# ParticleBase.net
KiCad netlist of a schematic drawn in EAGLE
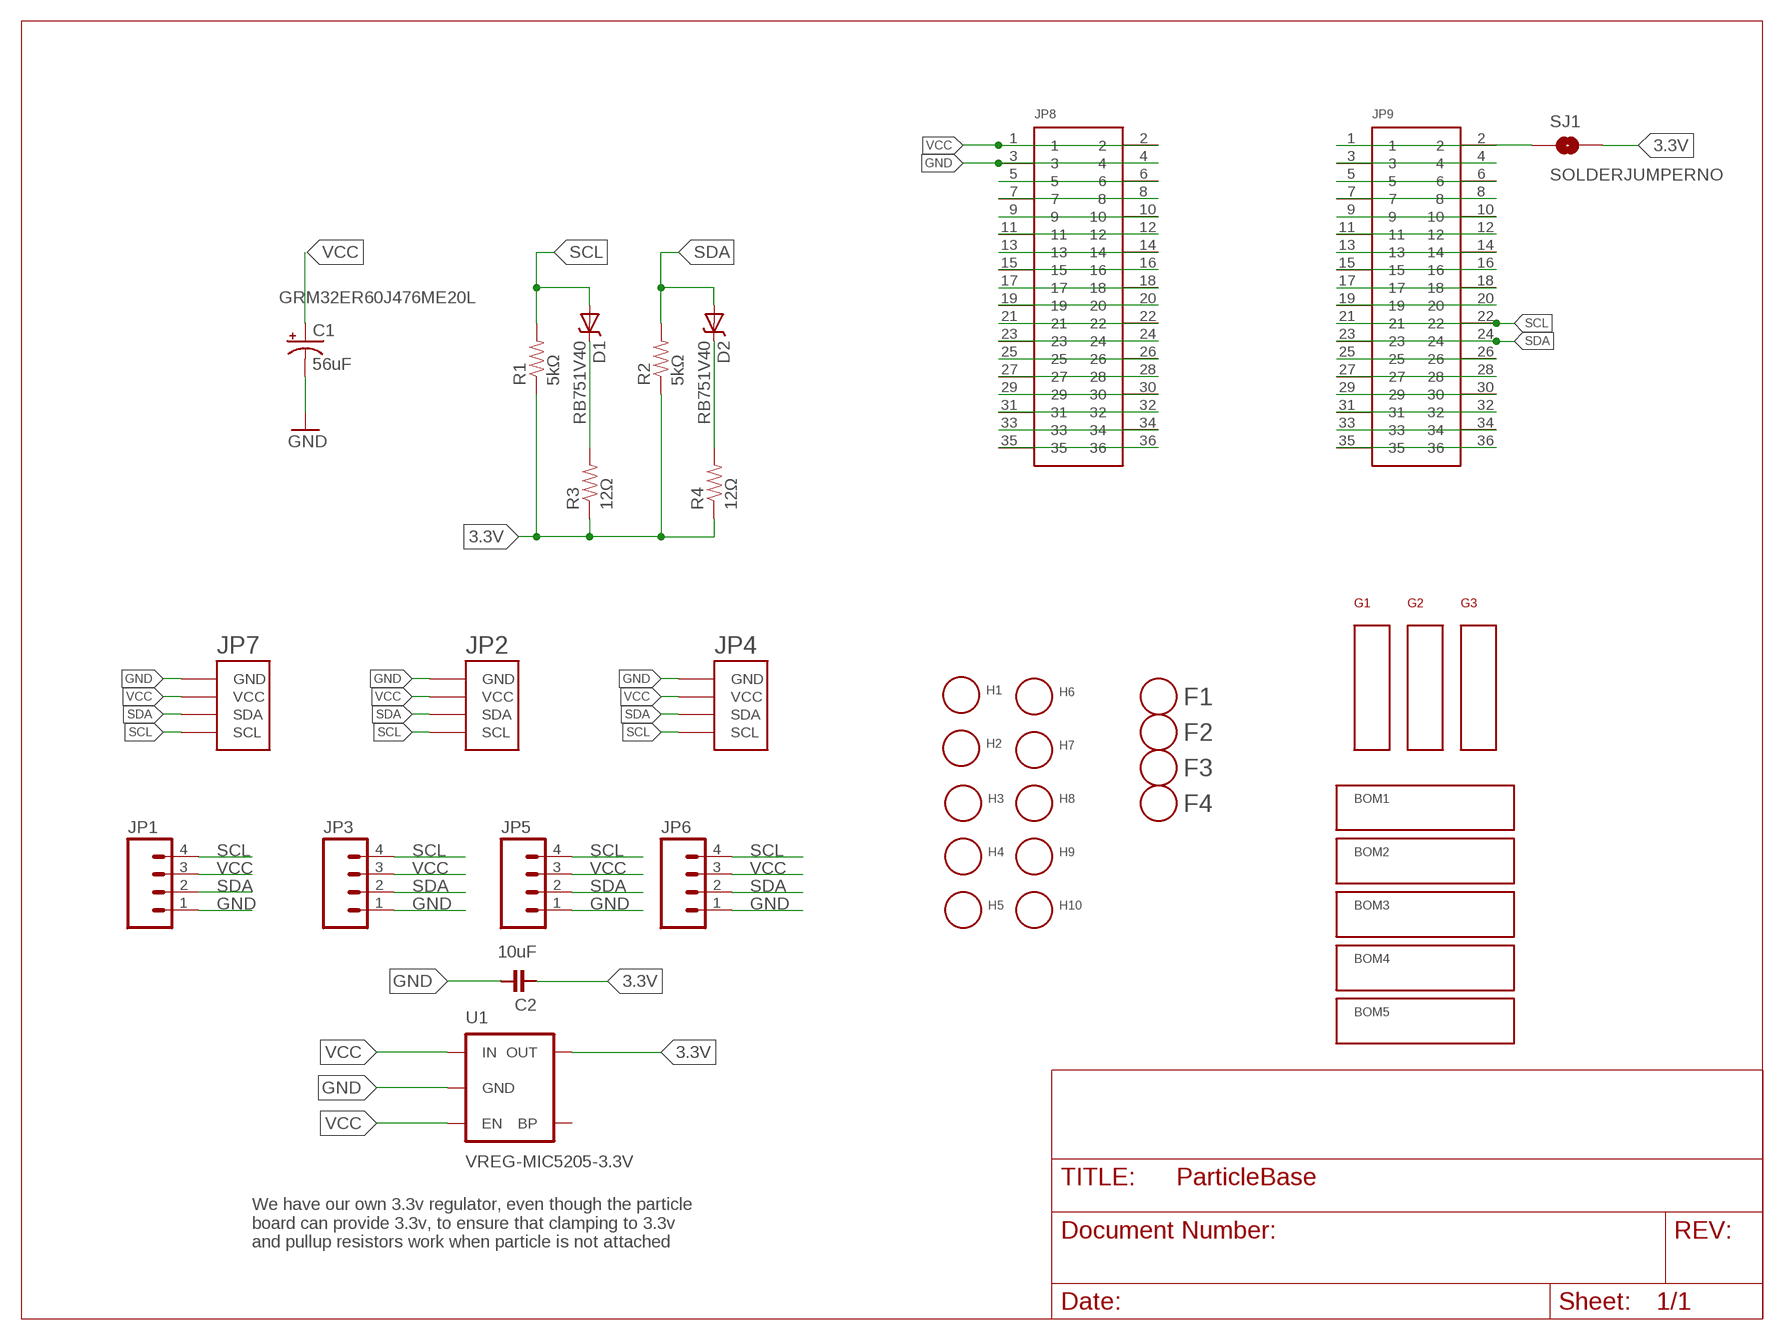
[diagram p0: schematic, sheet 1]

(export (version "E")
  (design (tool "Eeschema 10.0.6"))
  (components
    (comp (ref "C1")
      (value "56uF")
      (footprint "eagle-import:PANASONIC_D")
      (fields (field (name "PARTNUM") "EMVA250ADA560MF55G"))
      (libsource (lib "eagle-import") (part "CAPACITOR-POL-56UF-25V"))
    )
    (comp (ref "C2")
      (value "10uF")
      (footprint "eagle-import:0603")
      (fields (field (name "PARTNUM") "GRM188R61C106MA73D"))
      (libsource (lib "eagle-import") (part "CAPACITOR-10UF"))
    )
    (comp (ref "D1")
      (value "RB751V40")
      (footprint "eagle-import:SOD-323")
      (fields (field (name "PARTNUM") "BAT60A") (field (name "PARTNUM_1") "RB751V40"))
      (libsource (lib "eagle-import") (part "DIODE-SCHOTTKY-BAT60A"))
    )
    (comp (ref "D2")
      (value "RB751V40")
      (footprint "eagle-import:SOD-323")
      (fields (field (name "PARTNUM") "BAT60A") (field (name "PARTNUM_1") "RB751V40"))
      (libsource (lib "eagle-import") (part "DIODE-SCHOTTKY-BAT60A"))
    )
    (comp (ref "F1")
      (value "FIDUCIAL")
      (footprint "eagle-import:FIDUCIAL_1MM")
      (libsource (lib "eagle-import") (part "FIDUCIAL"))
    )
    (comp (ref "F2")
      (value "FIDUCIAL")
      (footprint "eagle-import:FIDUCIAL_1MM")
      (libsource (lib "eagle-import") (part "FIDUCIAL"))
    )
    (comp (ref "F3")
      (value "FIDUCIAL")
      (footprint "eagle-import:FIDUCIAL_1MM")
      (libsource (lib "eagle-import") (part "FIDUCIAL"))
    )
    (comp (ref "F4")
      (value "FIDUCIAL")
      (footprint "eagle-import:FIDUCIAL_1MM")
      (libsource (lib "eagle-import") (part "FIDUCIAL"))
    )
    (comp (ref "G1")
      (value "CARD-GUIDE")
      (footprint "eagle-import:CARD-GUIDE-2")
      (fields (field (name "PARTNUM") "HCG-201-165"))
      (libsource (lib "eagle-import") (part "CARD-GUIDE"))
    )
    (comp (ref "G2")
      (value "CARD-GUIDE")
      (footprint "eagle-import:CARD-GUIDE-2")
      (fields (field (name "PARTNUM") "HCG-202-165"))
      (libsource (lib "eagle-import") (part "CARD-GUIDE"))
    )
    (comp (ref "G3")
      (value "CARD-GUIDE")
      (footprint "eagle-import:CARD-GUIDE-2")
      (fields (field (name "PARTNUM") "HCG-201-165"))
      (libsource (lib "eagle-import") (part "CARD-GUIDE"))
    )
    (comp (ref "H1")
      (value "HOLE#2")
      (footprint "eagle-import:HOLE-#2")
      (fields (field (name "PARTNUM") "EXCLUDE"))
      (libsource (lib "eagle-import") (part "HOLE#2"))
    )
    (comp (ref "H2")
      (value "HOLE#2")
      (footprint "eagle-import:HOLE-#2")
      (fields (field (name "PARTNUM") "EXCLUDE"))
      (libsource (lib "eagle-import") (part "HOLE#2"))
    )
    (comp (ref "H3")
      (value "HOLE#2")
      (footprint "eagle-import:HOLE-#2")
      (fields (field (name "PARTNUM") "EXCLUDE"))
      (libsource (lib "eagle-import") (part "HOLE#2"))
    )
    (comp (ref "H4")
      (value "HOLE#2")
      (footprint "eagle-import:HOLE-#2")
      (fields (field (name "PARTNUM") "EXCLUDE"))
      (libsource (lib "eagle-import") (part "HOLE#2"))
    )
    (comp (ref "H5")
      (value "HOLE#2")
      (footprint "eagle-import:HOLE-#2")
      (fields (field (name "PARTNUM") "EXCLUDE"))
      (libsource (lib "eagle-import") (part "HOLE#2"))
    )
    (comp (ref "H6")
      (value "HOLE#2")
      (footprint "eagle-import:HOLE-#2")
      (fields (field (name "PARTNUM") "EXCLUDE"))
      (libsource (lib "eagle-import") (part "HOLE#2"))
    )
    (comp (ref "H7")
      (value "HOLE#2")
      (footprint "eagle-import:HOLE-#2")
      (fields (field (name "PARTNUM") "EXCLUDE"))
      (libsource (lib "eagle-import") (part "HOLE#2"))
    )
    (comp (ref "H8")
      (value "HOLE#2")
      (footprint "eagle-import:HOLE-#2")
      (fields (field (name "PARTNUM") "EXCLUDE"))
      (libsource (lib "eagle-import") (part "HOLE#2"))
    )
    (comp (ref "H9")
      (value "HOLE#2")
      (footprint "eagle-import:HOLE-#2")
      (fields (field (name "PARTNUM") "EXCLUDE"))
      (libsource (lib "eagle-import") (part "HOLE#2"))
    )
    (comp (ref "H10")
      (value "HOLE#2")
      (footprint "eagle-import:HOLE-#2")
      (fields (field (name "PARTNUM") "EXCLUDE"))
      (libsource (lib "eagle-import") (part "HOLE#2"))
    )
    (comp (ref "JP1")
      (value "M04LOCK")
      (footprint "eagle-import:1X04_LOCK")
      (fields (field (name "PARTNUM") "M20-9750446"))
      (libsource (lib "eagle-import") (part "M04LOCK"))
    )
    (comp (ref "JP2")
      (value "HEADER-MODULO")
      (footprint "eagle-import:JST-PA-SIDE-SMD")
      (fields (field (name "PARTNUM") "4P-SMD-2.0-90D"))
      (libsource (lib "eagle-import") (part "HEADER-MODULO"))
    )
    (comp (ref "JP3")
      (value "M04LOCK")
      (footprint "eagle-import:1X04_LOCK")
      (fields (field (name "PARTNUM") "M20-9750446"))
      (libsource (lib "eagle-import") (part "M04LOCK"))
    )
    (comp (ref "JP4")
      (value "HEADER-MODULO")
      (footprint "eagle-import:JST-PA-SIDE-SMD")
      (fields (field (name "PARTNUM") "4P-SMD-2.0-90D"))
      (libsource (lib "eagle-import") (part "HEADER-MODULO"))
    )
    (comp (ref "JP5")
      (value "M04LOCK")
      (footprint "eagle-import:1X04_LOCK")
      (fields (field (name "PARTNUM") "M20-9750446"))
      (libsource (lib "eagle-import") (part "M04LOCK"))
    )
    (comp (ref "JP6")
      (value "M04LOCK")
      (footprint "eagle-import:1X04_LOCK")
      (fields (field (name "PARTNUM") "M20-9750446"))
      (libsource (lib "eagle-import") (part "M04LOCK"))
    )
    (comp (ref "JP7")
      (value "HEADER-MODULO")
      (footprint "eagle-import:JST-PA-SIDE-SMD")
      (fields (field (name "PARTNUM") "4P-SMD-2.0-90D"))
      (libsource (lib "eagle-import") (part "HEADER-MODULO"))
    )
    (comp (ref "JP8")
      (value "HEADER-2X18")
      (footprint "eagle-import:2X18-LOCK")
      (fields (field (name "PARTNUM") "PPTC182LFBN-RC") (field (name "PARTNUM_1") "12x2 Receptacle"))
      (libsource (lib "eagle-import") (part "HEADER-2X18"))
    )
    (comp (ref "JP9")
      (value "HEADER-2X18")
      (footprint "eagle-import:2X18-LOCK")
      (fields (field (name "PARTNUM") "PPTC182LFBN-RC") (field (name "PARTNUM_1") "12x2 Receptacle"))
      (libsource (lib "eagle-import") (part "HEADER-2X18"))
    )
    (comp (ref "R1")
      (value "5kΩ")
      (footprint "eagle-import:0603")
      (fields (field (name "PARTNUM") "ERJ-3EKF5101V"))
      (libsource (lib "eagle-import") (part "RESISTOR-5KΩ"))
    )
    (comp (ref "R2")
      (value "5kΩ")
      (footprint "eagle-import:0603")
      (fields (field (name "PARTNUM") "ERJ-3EKF5101V"))
      (libsource (lib "eagle-import") (part "RESISTOR-5KΩ"))
    )
    (comp (ref "R3")
      (value "12Ω")
      (footprint "eagle-import:0603")
      (fields (field (name "PARTNUM") "ERJ-PA3J120V"))
      (libsource (lib "eagle-import") (part "RESISTOR-12Ω"))
    )
    (comp (ref "R4")
      (value "12Ω")
      (footprint "eagle-import:0603")
      (fields (field (name "PARTNUM") "ERJ-PA3J120V"))
      (libsource (lib "eagle-import") (part "RESISTOR-12Ω"))
    )
    (comp (ref "SJ1")
      (value "SOLDERJUMPERNO")
      (footprint "eagle-import:SJ_2S-NO")
      (libsource (lib "eagle-import") (part "SOLDERJUMPERNO"))
    )
    (comp (ref "U1")
      (value "VREG-MIC5205-3.3V")
      (footprint "eagle-import:SOT23-5")
      (fields (field (name "PARTNUM") "MIC5205-3.3YM5 TR"))
      (libsource (lib "eagle-import") (part "VREG-MIC5205-3.3V"))
    )
  )
  (nets
    (net (code "1") (name "3.3V") (class "Default")
      (node (ref "C2") (pin "2") (pinfunction "2_2") (pintype "passive"))
      (node (ref "R1") (pin "1") (pinfunction "1_1") (pintype "passive"))
      (node (ref "R2") (pin "1") (pinfunction "1_1") (pintype "passive"))
      (node (ref "R3") (pin "1") (pinfunction "1_1") (pintype "passive"))
      (node (ref "R4") (pin "1") (pinfunction "1_1") (pintype "passive"))
      (node (ref "SJ1") (pin "2") (pinfunction "2_2") (pintype "passive"))
      (node (ref "U1") (pin "5") (pinfunction "OUT_5") (pintype "passive"))
    )
    (net (code "2") (name "GND") (class "Default")
      (node (ref "C1") (pin "-") (pinfunction "-_-") (pintype "passive"))
      (node (ref "C2") (pin "1") (pinfunction "1_1") (pintype "passive"))
      (node (ref "JP1") (pin "1") (pinfunction "1_1") (pintype "passive"))
      (node (ref "JP2") (pin "1") (pinfunction "GND_1") (pintype "bidirectional"))
      (node (ref "JP3") (pin "1") (pinfunction "1_1") (pintype "passive"))
      (node (ref "JP4") (pin "1") (pinfunction "GND_1") (pintype "bidirectional"))
      (node (ref "JP5") (pin "1") (pinfunction "1_1") (pintype "passive"))
      (node (ref "JP6") (pin "1") (pinfunction "1_1") (pintype "passive"))
      (node (ref "JP7") (pin "1") (pinfunction "GND_1") (pintype "bidirectional"))
      (node (ref "JP8") (pin "3") (pinfunction "3_3") (pintype "bidirectional"))
      (node (ref "JP8") (pin "4") (pinfunction "4_4") (pintype "bidirectional"))
      (node (ref "U1") (pin "2") (pinfunction "GND_2") (pintype "input"))
    )
    (net (code "3") (name "Net-(D1-PadC)") (class "Default")
      (node (ref "D1") (pin "C") (pinfunction "C_C") (pintype "passive"))
      (node (ref "R3") (pin "2") (pinfunction "2_2") (pintype "passive"))
    )
    (net (code "4") (name "Net-(D2-PadC)") (class "Default")
      (node (ref "D2") (pin "C") (pinfunction "C_C") (pintype "passive"))
      (node (ref "R4") (pin "2") (pinfunction "2_2") (pintype "passive"))
    )
    (net (code "5") (name "Net-(JP8-Pad5)") (class "Default")
      (node (ref "JP8") (pin "5") (pinfunction "5_5") (pintype "bidirectional"))
      (node (ref "JP8") (pin "6") (pinfunction "6_6") (pintype "bidirectional"))
    )
    (net (code "6") (name "Net-(JP8-Pad7)") (class "Default")
      (node (ref "JP8") (pin "7") (pinfunction "7_7") (pintype "bidirectional"))
      (node (ref "JP8") (pin "8") (pinfunction "8_8") (pintype "bidirectional"))
    )
    (net (code "7") (name "Net-(JP8-Pad10)") (class "Default")
      (node (ref "JP8") (pin "10") (pinfunction "10_10") (pintype "bidirectional"))
      (node (ref "JP8") (pin "9") (pinfunction "9_9") (pintype "bidirectional"))
    )
    (net (code "8") (name "Net-(JP8-Pad11)") (class "Default")
      (node (ref "JP8") (pin "11") (pinfunction "11_11") (pintype "bidirectional"))
      (node (ref "JP8") (pin "12") (pinfunction "12_12") (pintype "bidirectional"))
    )
    (net (code "9") (name "Net-(JP8-Pad13)") (class "Default")
      (node (ref "JP8") (pin "13") (pinfunction "13_13") (pintype "bidirectional"))
      (node (ref "JP8") (pin "14") (pinfunction "14_14") (pintype "bidirectional"))
    )
    (net (code "10") (name "Net-(JP8-Pad15)") (class "Default")
      (node (ref "JP8") (pin "15") (pinfunction "15_15") (pintype "bidirectional"))
      (node (ref "JP8") (pin "16") (pinfunction "16_16") (pintype "bidirectional"))
    )
    (net (code "11") (name "Net-(JP8-Pad17)") (class "Default")
      (node (ref "JP8") (pin "17") (pinfunction "17_17") (pintype "bidirectional"))
      (node (ref "JP8") (pin "18") (pinfunction "18_18") (pintype "bidirectional"))
    )
    (net (code "12") (name "Net-(JP8-Pad19)") (class "Default")
      (node (ref "JP8") (pin "19") (pinfunction "19_19") (pintype "bidirectional"))
      (node (ref "JP8") (pin "20") (pinfunction "20_20") (pintype "bidirectional"))
    )
    (net (code "13") (name "Net-(JP8-Pad21)") (class "Default")
      (node (ref "JP8") (pin "21") (pinfunction "21_21") (pintype "bidirectional"))
      (node (ref "JP8") (pin "22") (pinfunction "22_22") (pintype "bidirectional"))
    )
    (net (code "14") (name "Net-(JP8-Pad23)") (class "Default")
      (node (ref "JP8") (pin "23") (pinfunction "23_23") (pintype "bidirectional"))
      (node (ref "JP8") (pin "24") (pinfunction "24_24") (pintype "bidirectional"))
    )
    (net (code "15") (name "Net-(JP8-Pad25)") (class "Default")
      (node (ref "JP8") (pin "25") (pinfunction "25_25") (pintype "bidirectional"))
      (node (ref "JP8") (pin "26") (pinfunction "26_26") (pintype "bidirectional"))
    )
    (net (code "16") (name "Net-(JP8-Pad27)") (class "Default")
      (node (ref "JP8") (pin "27") (pinfunction "27_27") (pintype "bidirectional"))
      (node (ref "JP8") (pin "28") (pinfunction "28_28") (pintype "bidirectional"))
    )
    (net (code "17") (name "Net-(JP8-Pad29)") (class "Default")
      (node (ref "JP8") (pin "29") (pinfunction "29_29") (pintype "bidirectional"))
      (node (ref "JP8") (pin "30") (pinfunction "30_30") (pintype "bidirectional"))
    )
    (net (code "18") (name "Net-(JP8-Pad31)") (class "Default")
      (node (ref "JP8") (pin "31") (pinfunction "31_31") (pintype "bidirectional"))
      (node (ref "JP8") (pin "32") (pinfunction "32_32") (pintype "bidirectional"))
    )
    (net (code "19") (name "Net-(JP8-Pad33)") (class "Default")
      (node (ref "JP8") (pin "33") (pinfunction "33_33") (pintype "bidirectional"))
      (node (ref "JP8") (pin "34") (pinfunction "34_34") (pintype "bidirectional"))
    )
    (net (code "20") (name "Net-(JP8-Pad35)") (class "Default")
      (node (ref "JP8") (pin "35") (pinfunction "35_35") (pintype "bidirectional"))
      (node (ref "JP8") (pin "36") (pinfunction "36_36") (pintype "bidirectional"))
    )
    (net (code "21") (name "Net-(JP9-Pad1)") (class "Default")
      (node (ref "JP9") (pin "1") (pinfunction "1_1") (pintype "bidirectional"))
      (node (ref "JP9") (pin "2") (pinfunction "2_2") (pintype "bidirectional"))
      (node (ref "SJ1") (pin "1") (pinfunction "1_1") (pintype "passive"))
    )
    (net (code "22") (name "Net-(JP9-Pad3)") (class "Default")
      (node (ref "JP9") (pin "3") (pinfunction "3_3") (pintype "bidirectional"))
      (node (ref "JP9") (pin "4") (pinfunction "4_4") (pintype "bidirectional"))
    )
    (net (code "23") (name "Net-(JP9-Pad5)") (class "Default")
      (node (ref "JP9") (pin "5") (pinfunction "5_5") (pintype "bidirectional"))
      (node (ref "JP9") (pin "6") (pinfunction "6_6") (pintype "bidirectional"))
    )
    (net (code "24") (name "Net-(JP9-Pad7)") (class "Default")
      (node (ref "JP9") (pin "7") (pinfunction "7_7") (pintype "bidirectional"))
      (node (ref "JP9") (pin "8") (pinfunction "8_8") (pintype "bidirectional"))
    )
    (net (code "25") (name "Net-(JP9-Pad10)") (class "Default")
      (node (ref "JP9") (pin "10") (pinfunction "10_10") (pintype "bidirectional"))
      (node (ref "JP9") (pin "9") (pinfunction "9_9") (pintype "bidirectional"))
    )
    (net (code "26") (name "Net-(JP9-Pad11)") (class "Default")
      (node (ref "JP9") (pin "11") (pinfunction "11_11") (pintype "bidirectional"))
      (node (ref "JP9") (pin "12") (pinfunction "12_12") (pintype "bidirectional"))
    )
    (net (code "27") (name "Net-(JP9-Pad13)") (class "Default")
      (node (ref "JP9") (pin "13") (pinfunction "13_13") (pintype "bidirectional"))
      (node (ref "JP9") (pin "14") (pinfunction "14_14") (pintype "bidirectional"))
    )
    (net (code "28") (name "Net-(JP9-Pad15)") (class "Default")
      (node (ref "JP9") (pin "15") (pinfunction "15_15") (pintype "bidirectional"))
      (node (ref "JP9") (pin "16") (pinfunction "16_16") (pintype "bidirectional"))
    )
    (net (code "29") (name "Net-(JP9-Pad17)") (class "Default")
      (node (ref "JP9") (pin "17") (pinfunction "17_17") (pintype "bidirectional"))
      (node (ref "JP9") (pin "18") (pinfunction "18_18") (pintype "bidirectional"))
    )
    (net (code "30") (name "Net-(JP9-Pad19)") (class "Default")
      (node (ref "JP9") (pin "19") (pinfunction "19_19") (pintype "bidirectional"))
      (node (ref "JP9") (pin "20") (pinfunction "20_20") (pintype "bidirectional"))
    )
    (net (code "31") (name "Net-(JP9-Pad25)") (class "Default")
      (node (ref "JP9") (pin "25") (pinfunction "25_25") (pintype "bidirectional"))
      (node (ref "JP9") (pin "26") (pinfunction "26_26") (pintype "bidirectional"))
    )
    (net (code "32") (name "Net-(JP9-Pad27)") (class "Default")
      (node (ref "JP9") (pin "27") (pinfunction "27_27") (pintype "bidirectional"))
      (node (ref "JP9") (pin "28") (pinfunction "28_28") (pintype "bidirectional"))
    )
    (net (code "33") (name "Net-(JP9-Pad29)") (class "Default")
      (node (ref "JP9") (pin "29") (pinfunction "29_29") (pintype "bidirectional"))
      (node (ref "JP9") (pin "30") (pinfunction "30_30") (pintype "bidirectional"))
    )
    (net (code "34") (name "Net-(JP9-Pad31)") (class "Default")
      (node (ref "JP9") (pin "31") (pinfunction "31_31") (pintype "bidirectional"))
      (node (ref "JP9") (pin "32") (pinfunction "32_32") (pintype "bidirectional"))
    )
    (net (code "35") (name "Net-(JP9-Pad33)") (class "Default")
      (node (ref "JP9") (pin "33") (pinfunction "33_33") (pintype "bidirectional"))
      (node (ref "JP9") (pin "34") (pinfunction "34_34") (pintype "bidirectional"))
    )
    (net (code "36") (name "Net-(JP9-Pad35)") (class "Default")
      (node (ref "JP9") (pin "35") (pinfunction "35_35") (pintype "bidirectional"))
      (node (ref "JP9") (pin "36") (pinfunction "36_36") (pintype "bidirectional"))
    )
    (net (code "37") (name "SCL") (class "Default")
      (node (ref "D1") (pin "A") (pinfunction "A_A") (pintype "passive"))
      (node (ref "JP1") (pin "4") (pinfunction "4_4") (pintype "passive"))
      (node (ref "JP2") (pin "4") (pinfunction "SCL_4") (pintype "bidirectional"))
      (node (ref "JP3") (pin "4") (pinfunction "4_4") (pintype "passive"))
      (node (ref "JP4") (pin "4") (pinfunction "SCL_4") (pintype "bidirectional"))
      (node (ref "JP5") (pin "4") (pinfunction "4_4") (pintype "passive"))
      (node (ref "JP6") (pin "4") (pinfunction "4_4") (pintype "passive"))
      (node (ref "JP7") (pin "4") (pinfunction "SCL_4") (pintype "bidirectional"))
      (node (ref "JP9") (pin "21") (pinfunction "21_21") (pintype "bidirectional"))
      (node (ref "JP9") (pin "22") (pinfunction "22_22") (pintype "bidirectional"))
      (node (ref "R1") (pin "2") (pinfunction "2_2") (pintype "passive"))
    )
    (net (code "38") (name "SDA") (class "Default")
      (node (ref "D2") (pin "A") (pinfunction "A_A") (pintype "passive"))
      (node (ref "JP1") (pin "2") (pinfunction "2_2") (pintype "passive"))
      (node (ref "JP2") (pin "3") (pinfunction "SDA_3") (pintype "bidirectional"))
      (node (ref "JP3") (pin "2") (pinfunction "2_2") (pintype "passive"))
      (node (ref "JP4") (pin "3") (pinfunction "SDA_3") (pintype "bidirectional"))
      (node (ref "JP5") (pin "2") (pinfunction "2_2") (pintype "passive"))
      (node (ref "JP6") (pin "2") (pinfunction "2_2") (pintype "passive"))
      (node (ref "JP7") (pin "3") (pinfunction "SDA_3") (pintype "bidirectional"))
      (node (ref "JP9") (pin "23") (pinfunction "23_23") (pintype "bidirectional"))
      (node (ref "JP9") (pin "24") (pinfunction "24_24") (pintype "bidirectional"))
      (node (ref "R2") (pin "2") (pinfunction "2_2") (pintype "passive"))
    )
    (net (code "39") (name "VCC") (class "Default")
      (node (ref "C1") (pin "+") (pinfunction "+_+") (pintype "passive"))
      (node (ref "JP1") (pin "3") (pinfunction "3_3") (pintype "passive"))
      (node (ref "JP2") (pin "2") (pinfunction "VCC_2") (pintype "bidirectional"))
      (node (ref "JP3") (pin "3") (pinfunction "3_3") (pintype "passive"))
      (node (ref "JP4") (pin "2") (pinfunction "VCC_2") (pintype "bidirectional"))
      (node (ref "JP5") (pin "3") (pinfunction "3_3") (pintype "passive"))
      (node (ref "JP6") (pin "3") (pinfunction "3_3") (pintype "passive"))
      (node (ref "JP7") (pin "2") (pinfunction "VCC_2") (pintype "bidirectional"))
      (node (ref "JP8") (pin "1") (pinfunction "1_1") (pintype "bidirectional"))
      (node (ref "JP8") (pin "2") (pinfunction "2_2") (pintype "bidirectional"))
      (node (ref "U1") (pin "1") (pinfunction "IN_1") (pintype "input"))
      (node (ref "U1") (pin "3") (pinfunction "EN_3") (pintype "input"))
    )
    (net (code "40") (name "unconnected-(H1-HOLE-PadP$1)") (class "Default")
      (node (ref "H1") (pin "P$1") (pinfunction "HOLE_P$1") (pintype "bidirectional"))
    )
    (net (code "41") (name "unconnected-(H2-HOLE-PadP$1)") (class "Default")
      (node (ref "H2") (pin "P$1") (pinfunction "HOLE_P$1") (pintype "bidirectional"))
    )
    (net (code "42") (name "unconnected-(H3-HOLE-PadP$1)") (class "Default")
      (node (ref "H3") (pin "P$1") (pinfunction "HOLE_P$1") (pintype "bidirectional"))
    )
    (net (code "43") (name "unconnected-(H4-HOLE-PadP$1)") (class "Default")
      (node (ref "H4") (pin "P$1") (pinfunction "HOLE_P$1") (pintype "bidirectional"))
    )
    (net (code "44") (name "unconnected-(H5-HOLE-PadP$1)") (class "Default")
      (node (ref "H5") (pin "P$1") (pinfunction "HOLE_P$1") (pintype "bidirectional"))
    )
    (net (code "45") (name "unconnected-(H6-HOLE-PadP$1)") (class "Default")
      (node (ref "H6") (pin "P$1") (pinfunction "HOLE_P$1") (pintype "bidirectional"))
    )
    (net (code "46") (name "unconnected-(H7-HOLE-PadP$1)") (class "Default")
      (node (ref "H7") (pin "P$1") (pinfunction "HOLE_P$1") (pintype "bidirectional"))
    )
    (net (code "47") (name "unconnected-(H8-HOLE-PadP$1)") (class "Default")
      (node (ref "H8") (pin "P$1") (pinfunction "HOLE_P$1") (pintype "bidirectional"))
    )
    (net (code "48") (name "unconnected-(H9-HOLE-PadP$1)") (class "Default")
      (node (ref "H9") (pin "P$1") (pinfunction "HOLE_P$1") (pintype "bidirectional"))
    )
    (net (code "49") (name "unconnected-(H10-HOLE-PadP$1)") (class "Default")
      (node (ref "H10") (pin "P$1") (pinfunction "HOLE_P$1") (pintype "bidirectional"))
    )
    (net (code "50") (name "unconnected-(U1-BP-Pad4)") (class "Default")
      (node (ref "U1") (pin "4") (pinfunction "BP_4") (pintype "input"))
    )
  )
)
